# FPGA_MGT.net
KiCad netlist of a schematic drawn in Altium Designer
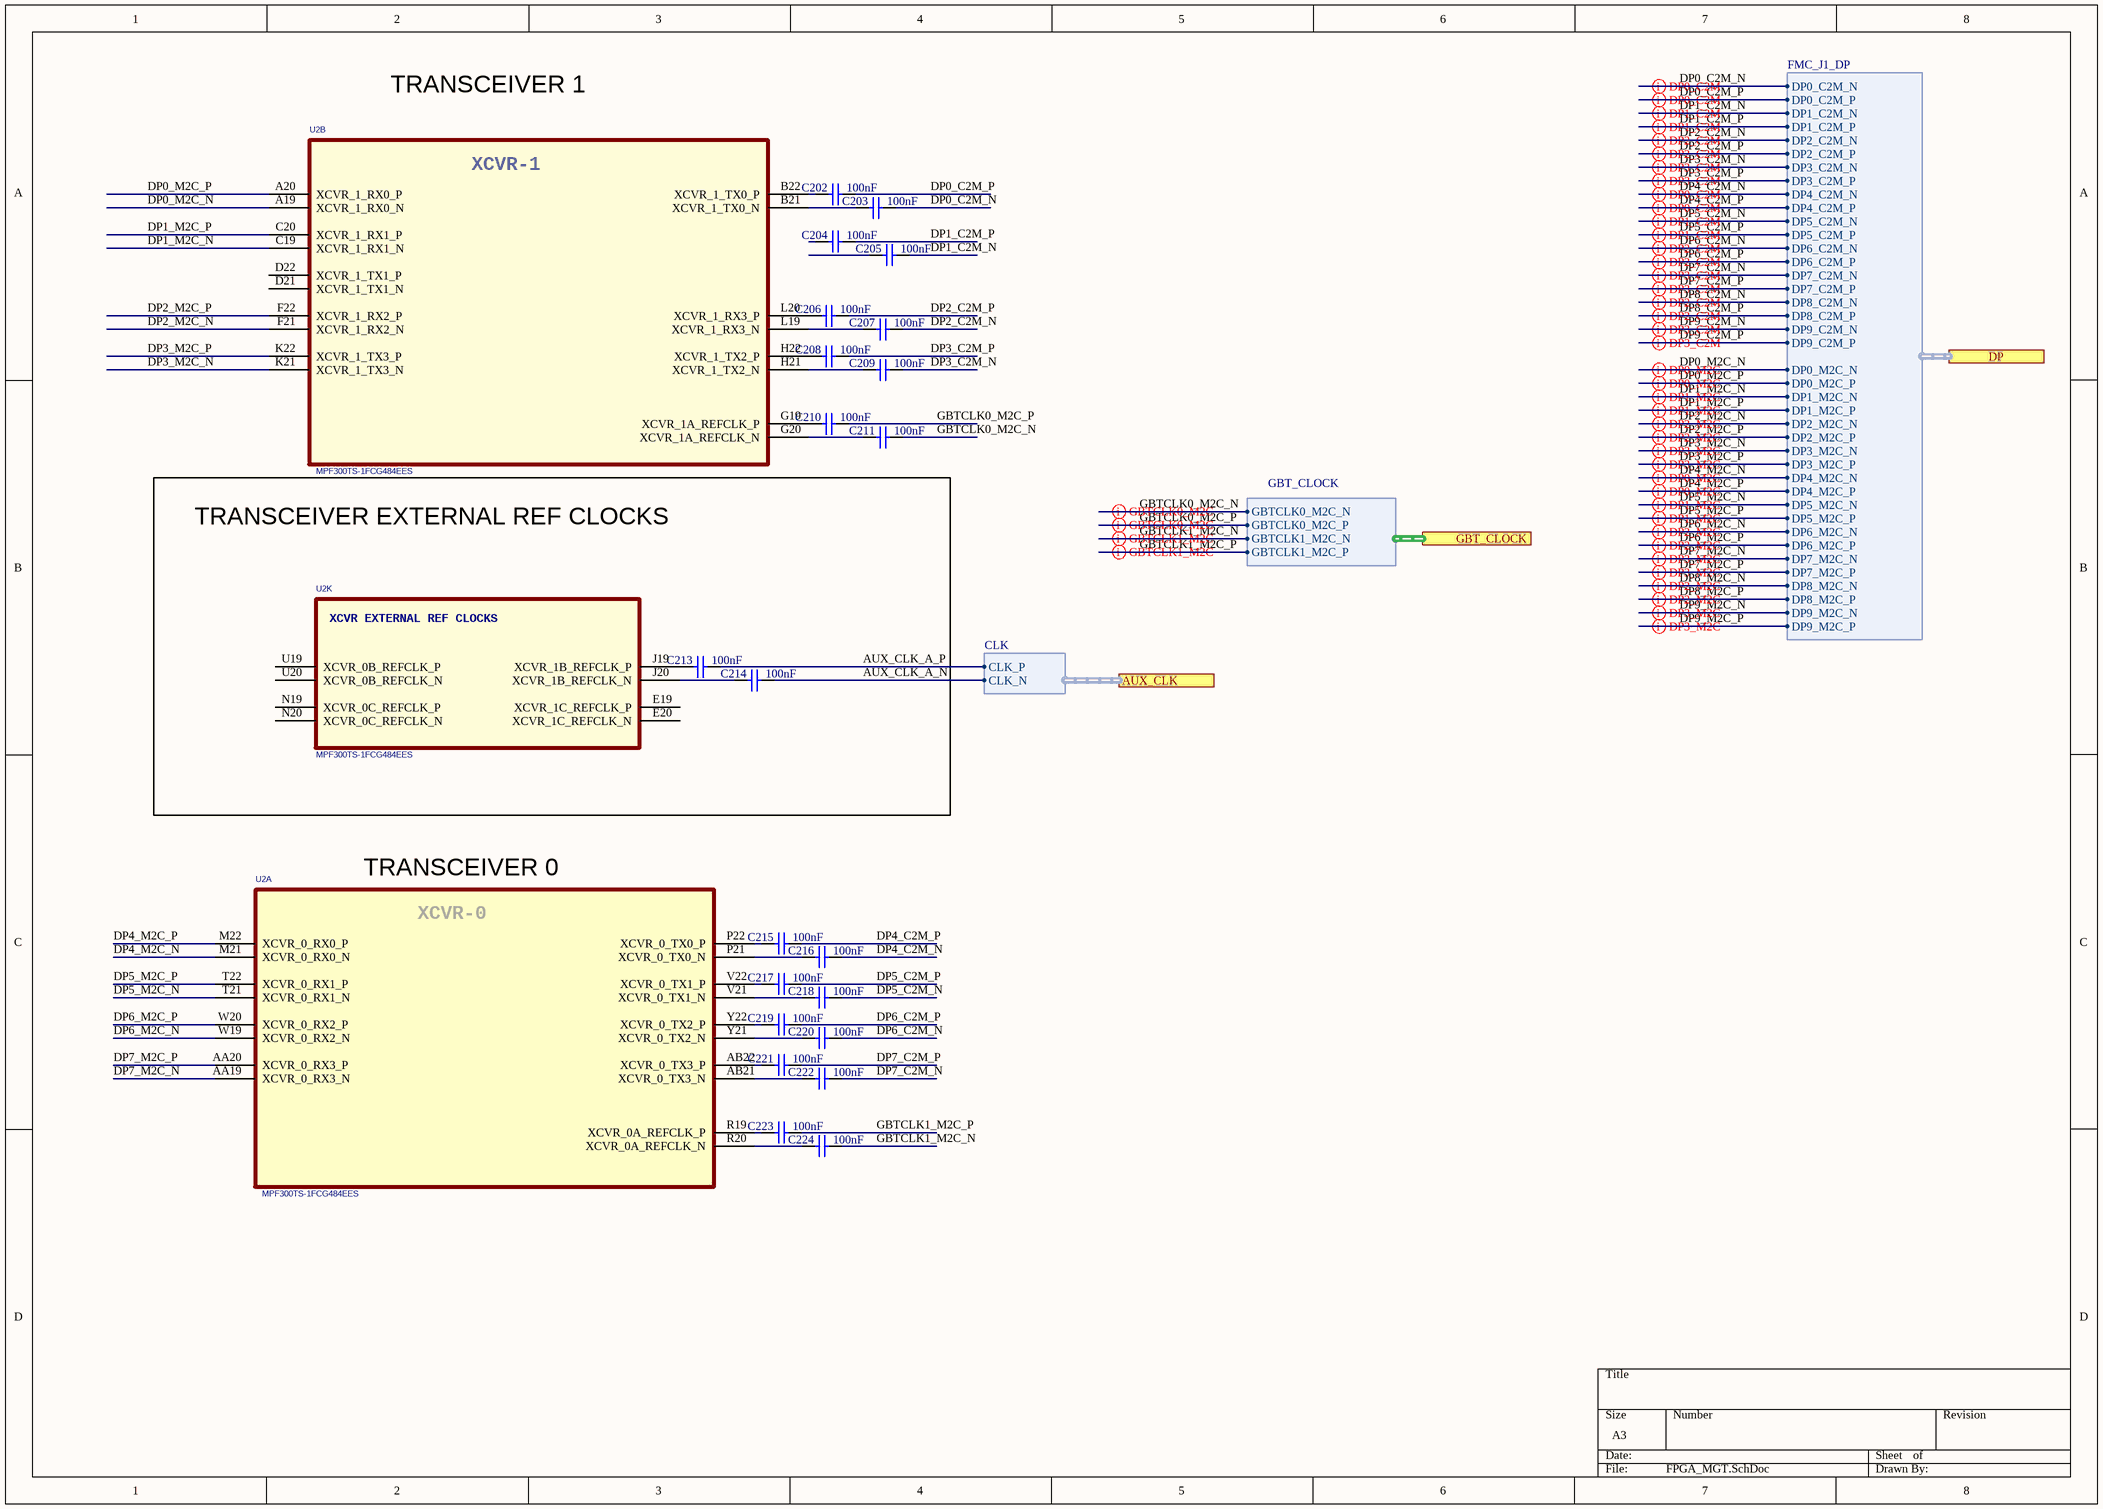
[diagram p0: FPGA_MGT.SchDoc]

(export (version "E")
  (design (tool "Eeschema 10.0.6"))
  (components
    (comp (ref "C202")
      (value "100nF")
      (footprint "CAPC0603X33N")
      (description "Non-polarised capacitor")
      (fields
        (field (name "PART NUMBER") "CC0201_100NF_6.3V_10%_X5R")
        (field (name "VOLTAGE") "6.3V")
        (field (name "AUTHOR") "CERN DEM JLC")
      )
      (libsource (lib "Capacitors") (part "Capacitor - non polarized"))
    )
    (comp (ref "C203")
      (value "100nF")
      (footprint "CAPC0603X33N")
      (description "Non-polarised capacitor")
      (fields
        (field (name "PART NUMBER") "CC0201_100NF_6.3V_10%_X5R")
        (field (name "VOLTAGE") "6.3V")
        (field (name "AUTHOR") "CERN DEM JLC")
      )
      (libsource (lib "Capacitors") (part "Capacitor - non polarized"))
    )
    (comp (ref "C204")
      (value "100nF")
      (footprint "CAPC0603X33N")
      (description "Non-polarised capacitor")
      (fields
        (field (name "PART NUMBER") "CC0201_100NF_6.3V_10%_X5R")
        (field (name "VOLTAGE") "6.3V")
        (field (name "AUTHOR") "CERN DEM JLC")
      )
      (libsource (lib "Capacitors") (part "Capacitor - non polarized"))
    )
    (comp (ref "C205")
      (value "100nF")
      (footprint "CAPC0603X33N")
      (description "Non-polarised capacitor")
      (fields
        (field (name "PART NUMBER") "CC0201_100NF_6.3V_10%_X5R")
        (field (name "VOLTAGE") "6.3V")
        (field (name "AUTHOR") "CERN DEM JLC")
      )
      (libsource (lib "Capacitors") (part "Capacitor - non polarized"))
    )
    (comp (ref "C206")
      (value "100nF")
      (footprint "CAPC0603X33N")
      (description "Non-polarised capacitor")
      (fields
        (field (name "PART NUMBER") "CC0201_100NF_6.3V_10%_X5R")
        (field (name "VOLTAGE") "6.3V")
        (field (name "AUTHOR") "CERN DEM JLC")
      )
      (libsource (lib "Capacitors") (part "Capacitor - non polarized"))
    )
    (comp (ref "C207")
      (value "100nF")
      (footprint "CAPC0603X33N")
      (description "Non-polarised capacitor")
      (fields
        (field (name "PART NUMBER") "CC0201_100NF_6.3V_10%_X5R")
        (field (name "VOLTAGE") "6.3V")
        (field (name "AUTHOR") "CERN DEM JLC")
      )
      (libsource (lib "Capacitors") (part "Capacitor - non polarized"))
    )
    (comp (ref "C208")
      (value "100nF")
      (footprint "CAPC0603X33N")
      (description "Non-polarised capacitor")
      (fields
        (field (name "PART NUMBER") "CC0201_100NF_6.3V_10%_X5R")
        (field (name "VOLTAGE") "6.3V")
        (field (name "AUTHOR") "CERN DEM JLC")
      )
      (libsource (lib "Capacitors") (part "Capacitor - non polarized"))
    )
    (comp (ref "C209")
      (value "100nF")
      (footprint "CAPC0603X33N")
      (description "Non-polarised capacitor")
      (fields
        (field (name "PART NUMBER") "CC0201_100NF_6.3V_10%_X5R")
        (field (name "VOLTAGE") "6.3V")
        (field (name "AUTHOR") "CERN DEM JLC")
      )
      (libsource (lib "Capacitors") (part "Capacitor - non polarized"))
    )
    (comp (ref "C210")
      (value "100nF")
      (footprint "CAPC0603X33N")
      (description "Non-polarised capacitor")
      (fields
        (field (name "PART NUMBER") "CC0201_100NF_6.3V_10%_X5R")
        (field (name "VOLTAGE") "6.3V")
        (field (name "AUTHOR") "CERN DEM JLC")
      )
      (libsource (lib "Capacitors") (part "Capacitor - non polarized"))
    )
    (comp (ref "C211")
      (value "100nF")
      (footprint "CAPC0603X33N")
      (description "Non-polarised capacitor")
      (fields
        (field (name "PART NUMBER") "CC0201_100NF_6.3V_10%_X5R")
        (field (name "VOLTAGE") "6.3V")
        (field (name "AUTHOR") "CERN DEM JLC")
      )
      (libsource (lib "Capacitors") (part "Capacitor - non polarized"))
    )
    (comp (ref "C213")
      (value "100nF")
      (footprint "CAPC0603X33N")
      (description "Non-polarised capacitor")
      (fields
        (field (name "PART NUMBER") "CC0201_100NF_6.3V_10%_X5R")
        (field (name "VOLTAGE") "6.3V")
        (field (name "AUTHOR") "CERN DEM JLC")
      )
      (libsource (lib "Capacitors") (part "Capacitor - non polarized"))
    )
    (comp (ref "C214")
      (value "100nF")
      (footprint "CAPC0603X33N")
      (description "Non-polarised capacitor")
      (fields
        (field (name "PART NUMBER") "CC0201_100NF_6.3V_10%_X5R")
        (field (name "VOLTAGE") "6.3V")
        (field (name "AUTHOR") "CERN DEM JLC")
      )
      (libsource (lib "Capacitors") (part "Capacitor - non polarized"))
    )
    (comp (ref "C215")
      (value "100nF")
      (footprint "CAPC0603X33N")
      (description "Non-polarised capacitor")
      (fields
        (field (name "PART NUMBER") "CC0201_100NF_6.3V_10%_X5R")
        (field (name "VOLTAGE") "6.3V")
        (field (name "AUTHOR") "CERN DEM JLC")
      )
      (libsource (lib "Capacitors") (part "Capacitor - non polarized"))
    )
    (comp (ref "C216")
      (value "100nF")
      (footprint "CAPC0603X33N")
      (description "Non-polarised capacitor")
      (fields
        (field (name "PART NUMBER") "CC0201_100NF_6.3V_10%_X5R")
        (field (name "VOLTAGE") "6.3V")
        (field (name "AUTHOR") "CERN DEM JLC")
      )
      (libsource (lib "Capacitors") (part "Capacitor - non polarized"))
    )
    (comp (ref "C217")
      (value "100nF")
      (footprint "CAPC0603X33N")
      (description "Non-polarised capacitor")
      (fields
        (field (name "PART NUMBER") "CC0201_100NF_6.3V_10%_X5R")
        (field (name "VOLTAGE") "6.3V")
        (field (name "AUTHOR") "CERN DEM JLC")
      )
      (libsource (lib "Capacitors") (part "Capacitor - non polarized"))
    )
    (comp (ref "C218")
      (value "100nF")
      (footprint "CAPC0603X33N")
      (description "Non-polarised capacitor")
      (fields
        (field (name "PART NUMBER") "CC0201_100NF_6.3V_10%_X5R")
        (field (name "VOLTAGE") "6.3V")
        (field (name "AUTHOR") "CERN DEM JLC")
      )
      (libsource (lib "Capacitors") (part "Capacitor - non polarized"))
    )
    (comp (ref "C219")
      (value "100nF")
      (footprint "CAPC0603X33N")
      (description "Non-polarised capacitor")
      (fields
        (field (name "PART NUMBER") "CC0201_100NF_6.3V_10%_X5R")
        (field (name "VOLTAGE") "6.3V")
        (field (name "AUTHOR") "CERN DEM JLC")
      )
      (libsource (lib "Capacitors") (part "Capacitor - non polarized"))
    )
    (comp (ref "C220")
      (value "100nF")
      (footprint "CAPC0603X33N")
      (description "Non-polarised capacitor")
      (fields
        (field (name "PART NUMBER") "CC0201_100NF_6.3V_10%_X5R")
        (field (name "VOLTAGE") "6.3V")
        (field (name "AUTHOR") "CERN DEM JLC")
      )
      (libsource (lib "Capacitors") (part "Capacitor - non polarized"))
    )
    (comp (ref "C221")
      (value "100nF")
      (footprint "CAPC0603X33N")
      (description "Non-polarised capacitor")
      (fields
        (field (name "PART NUMBER") "CC0201_100NF_6.3V_10%_X5R")
        (field (name "VOLTAGE") "6.3V")
        (field (name "AUTHOR") "CERN DEM JLC")
      )
      (libsource (lib "Capacitors") (part "Capacitor - non polarized"))
    )
    (comp (ref "C222")
      (value "100nF")
      (footprint "CAPC0603X33N")
      (description "Non-polarised capacitor")
      (fields
        (field (name "PART NUMBER") "CC0201_100NF_6.3V_10%_X5R")
        (field (name "VOLTAGE") "6.3V")
        (field (name "AUTHOR") "CERN DEM JLC")
      )
      (libsource (lib "Capacitors") (part "Capacitor - non polarized"))
    )
    (comp (ref "C223")
      (value "100nF")
      (footprint "CAPC0603X33N")
      (description "Non-polarised capacitor")
      (fields
        (field (name "PART NUMBER") "CC0201_100NF_6.3V_10%_X5R")
        (field (name "VOLTAGE") "6.3V")
        (field (name "AUTHOR") "CERN DEM JLC")
      )
      (libsource (lib "Capacitors") (part "Capacitor - non polarized"))
    )
    (comp (ref "C224")
      (value "100nF")
      (footprint "CAPC0603X33N")
      (description "Non-polarised capacitor")
      (fields
        (field (name "PART NUMBER") "CC0201_100NF_6.3V_10%_X5R")
        (field (name "VOLTAGE") "6.3V")
        (field (name "AUTHOR") "CERN DEM JLC")
      )
      (libsource (lib "Capacitors") (part "Capacitor - non polarized"))
    )
    (comp (ref "U2")
      (value "MPF300TS-1FCG484EES")
      (footprint "BGA484C100P22X22_2300X2300X320")
      (description "FCG484,23mmX23mm,1.0mm pitch")
      (fields (field (name "MANUFACTURER") "Microsemi") (field (name "PART NUMBER") "MPF300TS-1FCG484I"))
      (libsource (lib "LIBRARY_SCH") (part "FPGA_MPF300T-FCG484"))
    )
  )
  (nets
    (net (code "4") (name "/AUX_CLK_A_N") (class "Default")
      (node (ref "C214") (pin "2") (pinfunction "2_2") (pintype "passive"))
    )
    (net (code "5") (name "/AUX_CLK_A_P") (class "Default")
      (node (ref "C213") (pin "2") (pinfunction "2_2") (pintype "passive"))
    )
    (net (code "6") (name "/DP0_C2M_N") (class "Default")
      (node (ref "C203") (pin "2") (pinfunction "2_2") (pintype "passive"))
    )
    (net (code "7") (name "/DP0_C2M_P") (class "Default")
      (node (ref "C202") (pin "2") (pinfunction "2_2") (pintype "passive"))
    )
    (net (code "8") (name "/DP0_M2C_N") (class "Default")
      (node (ref "U2") (pin "A19") (pinfunction "XCVR_1_RX0_N_A19") (pintype "passive"))
    )
    (net (code "9") (name "/DP0_M2C_P") (class "Default")
      (node (ref "U2") (pin "A20") (pinfunction "XCVR_1_RX0_P_A20") (pintype "passive"))
    )
    (net (code "10") (name "/DP1_C2M_N") (class "Default")
      (node (ref "C205") (pin "2") (pinfunction "2_2") (pintype "passive"))
    )
    (net (code "11") (name "/DP1_C2M_P") (class "Default")
      (node (ref "C204") (pin "2") (pinfunction "2_2") (pintype "passive"))
    )
    (net (code "12") (name "/DP1_M2C_N") (class "Default")
      (node (ref "U2") (pin "C19") (pinfunction "XCVR_1_RX1_N_C19") (pintype "passive"))
    )
    (net (code "13") (name "/DP1_M2C_P") (class "Default")
      (node (ref "U2") (pin "C20") (pinfunction "XCVR_1_RX1_P_C20") (pintype "passive"))
    )
    (net (code "14") (name "/DP2_C2M_N") (class "Default")
      (node (ref "C207") (pin "2") (pinfunction "2_2") (pintype "passive"))
    )
    (net (code "15") (name "/DP2_C2M_P") (class "Default")
      (node (ref "C206") (pin "2") (pinfunction "2_2") (pintype "passive"))
    )
    (net (code "16") (name "/DP2_M2C_N") (class "Default")
      (node (ref "U2") (pin "F21") (pinfunction "XCVR_1_RX2_N_F21") (pintype "passive"))
    )
    (net (code "17") (name "/DP2_M2C_P") (class "Default")
      (node (ref "U2") (pin "F22") (pinfunction "XCVR_1_RX2_P_F22") (pintype "passive"))
    )
    (net (code "18") (name "/DP3_C2M_N") (class "Default")
      (node (ref "C209") (pin "2") (pinfunction "2_2") (pintype "passive"))
    )
    (net (code "19") (name "/DP3_C2M_P") (class "Default")
      (node (ref "C208") (pin "2") (pinfunction "2_2") (pintype "passive"))
    )
    (net (code "20") (name "/DP3_M2C_N") (class "Default")
      (node (ref "U2") (pin "K21") (pinfunction "XCVR_1_TX3_N_K21") (pintype "passive"))
    )
    (net (code "21") (name "/DP3_M2C_P") (class "Default")
      (node (ref "U2") (pin "K22") (pinfunction "XCVR_1_TX3_P_K22") (pintype "passive"))
    )
    (net (code "22") (name "/DP4_C2M_N") (class "Default")
      (node (ref "C216") (pin "2") (pinfunction "2_2") (pintype "passive"))
    )
    (net (code "23") (name "/DP4_C2M_P") (class "Default")
      (node (ref "C215") (pin "2") (pinfunction "2_2") (pintype "passive"))
    )
    (net (code "24") (name "/DP4_M2C_N") (class "Default")
      (node (ref "U2") (pin "M21") (pinfunction "XCVR_0_RX0_N_M21") (pintype "passive"))
    )
    (net (code "25") (name "/DP4_M2C_P") (class "Default")
      (node (ref "U2") (pin "M22") (pinfunction "XCVR_0_RX0_P_M22") (pintype "passive"))
    )
    (net (code "26") (name "/DP5_C2M_N") (class "Default")
      (node (ref "C218") (pin "2") (pinfunction "2_2") (pintype "passive"))
    )
    (net (code "27") (name "/DP5_C2M_P") (class "Default")
      (node (ref "C217") (pin "2") (pinfunction "2_2") (pintype "passive"))
    )
    (net (code "28") (name "/DP5_M2C_N") (class "Default")
      (node (ref "U2") (pin "T21") (pinfunction "XCVR_0_RX1_N_T21") (pintype "passive"))
    )
    (net (code "29") (name "/DP5_M2C_P") (class "Default")
      (node (ref "U2") (pin "T22") (pinfunction "XCVR_0_RX1_P_T22") (pintype "passive"))
    )
    (net (code "30") (name "/DP6_C2M_N") (class "Default")
      (node (ref "C220") (pin "2") (pinfunction "2_2") (pintype "passive"))
    )
    (net (code "31") (name "/DP6_C2M_P") (class "Default")
      (node (ref "C219") (pin "2") (pinfunction "2_2") (pintype "passive"))
    )
    (net (code "32") (name "/DP6_M2C_N") (class "Default")
      (node (ref "U2") (pin "W19") (pinfunction "XCVR_0_RX2_N_W19") (pintype "passive"))
    )
    (net (code "33") (name "/DP6_M2C_P") (class "Default")
      (node (ref "U2") (pin "W20") (pinfunction "XCVR_0_RX2_P_W20") (pintype "passive"))
    )
    (net (code "34") (name "/DP7_C2M_N") (class "Default")
      (node (ref "C222") (pin "2") (pinfunction "2_2") (pintype "passive"))
    )
    (net (code "35") (name "/DP7_C2M_P") (class "Default")
      (node (ref "C221") (pin "2") (pinfunction "2_2") (pintype "passive"))
    )
    (net (code "36") (name "/DP7_M2C_N") (class "Default")
      (node (ref "U2") (pin "AA19") (pinfunction "XCVR_0_RX3_N_AA19") (pintype "passive"))
    )
    (net (code "37") (name "/DP7_M2C_P") (class "Default")
      (node (ref "U2") (pin "AA20") (pinfunction "XCVR_0_RX3_P_AA20") (pintype "passive"))
    )
    (net (code "46") (name "/GBTCLK0_M2C_N") (class "Default")
      (node (ref "C211") (pin "2") (pinfunction "2_2") (pintype "passive"))
    )
    (net (code "47") (name "/GBTCLK0_M2C_P") (class "Default")
      (node (ref "C210") (pin "2") (pinfunction "2_2") (pintype "passive"))
    )
    (net (code "48") (name "/GBTCLK1_M2C_N") (class "Default")
      (node (ref "C224") (pin "2") (pinfunction "2_2") (pintype "passive"))
    )
    (net (code "49") (name "/GBTCLK1_M2C_P") (class "Default")
      (node (ref "C223") (pin "2") (pinfunction "2_2") (pintype "passive"))
    )
    (net (code "53") (name "Net-(U2A-XCVR_0A_REFCLK_N)") (class "Default")
      (node (ref "C224") (pin "1") (pinfunction "1_1") (pintype "passive"))
      (node (ref "U2") (pin "R20") (pinfunction "XCVR_0A_REFCLK_N_R20") (pintype "passive"))
    )
    (net (code "54") (name "Net-(U2A-XCVR_0A_REFCLK_P)") (class "Default")
      (node (ref "C223") (pin "1") (pinfunction "1_1") (pintype "passive"))
      (node (ref "U2") (pin "R19") (pinfunction "XCVR_0A_REFCLK_P_R19") (pintype "passive"))
    )
    (net (code "55") (name "Net-(U2A-XCVR_0_TX0_N)") (class "Default")
      (node (ref "C216") (pin "1") (pinfunction "1_1") (pintype "passive"))
      (node (ref "U2") (pin "P21") (pinfunction "XCVR_0_TX0_N_P21") (pintype "passive"))
    )
    (net (code "56") (name "Net-(U2A-XCVR_0_TX0_P)") (class "Default")
      (node (ref "C215") (pin "1") (pinfunction "1_1") (pintype "passive"))
      (node (ref "U2") (pin "P22") (pinfunction "XCVR_0_TX0_P_P22") (pintype "passive"))
    )
    (net (code "57") (name "Net-(U2A-XCVR_0_TX1_N)") (class "Default")
      (node (ref "C218") (pin "1") (pinfunction "1_1") (pintype "passive"))
      (node (ref "U2") (pin "V21") (pinfunction "XCVR_0_TX1_N_V21") (pintype "passive"))
    )
    (net (code "58") (name "Net-(U2A-XCVR_0_TX1_P)") (class "Default")
      (node (ref "C217") (pin "1") (pinfunction "1_1") (pintype "passive"))
      (node (ref "U2") (pin "V22") (pinfunction "XCVR_0_TX1_P_V22") (pintype "passive"))
    )
    (net (code "59") (name "Net-(U2A-XCVR_0_TX2_N)") (class "Default")
      (node (ref "C220") (pin "1") (pinfunction "1_1") (pintype "passive"))
      (node (ref "U2") (pin "Y21") (pinfunction "XCVR_0_TX2_N_Y21") (pintype "passive"))
    )
    (net (code "60") (name "Net-(U2A-XCVR_0_TX2_P)") (class "Default")
      (node (ref "C219") (pin "1") (pinfunction "1_1") (pintype "passive"))
      (node (ref "U2") (pin "Y22") (pinfunction "XCVR_0_TX2_P_Y22") (pintype "passive"))
    )
    (net (code "61") (name "Net-(U2A-XCVR_0_TX3_N)") (class "Default")
      (node (ref "C222") (pin "1") (pinfunction "1_1") (pintype "passive"))
      (node (ref "U2") (pin "AB21") (pinfunction "XCVR_0_TX3_N_AB21") (pintype "passive"))
    )
    (net (code "62") (name "Net-(U2A-XCVR_0_TX3_P)") (class "Default")
      (node (ref "C221") (pin "1") (pinfunction "1_1") (pintype "passive"))
      (node (ref "U2") (pin "AB22") (pinfunction "XCVR_0_TX3_P_AB22") (pintype "passive"))
    )
    (net (code "63") (name "Net-(U2B-XCVR_1A_REFCLK_N)") (class "Default")
      (node (ref "C211") (pin "1") (pinfunction "1_1") (pintype "passive"))
      (node (ref "U2") (pin "G20") (pinfunction "XCVR_1A_REFCLK_N_G20") (pintype "passive"))
    )
    (net (code "64") (name "Net-(U2B-XCVR_1A_REFCLK_P)") (class "Default")
      (node (ref "C210") (pin "1") (pinfunction "1_1") (pintype "passive"))
      (node (ref "U2") (pin "G19") (pinfunction "XCVR_1A_REFCLK_P_G19") (pintype "passive"))
    )
    (net (code "65") (name "Net-(U2B-XCVR_1_RX3_N)") (class "Default")
      (node (ref "C207") (pin "1") (pinfunction "1_1") (pintype "passive"))
      (node (ref "U2") (pin "L19") (pinfunction "XCVR_1_RX3_N_L19") (pintype "passive"))
    )
    (net (code "66") (name "Net-(U2B-XCVR_1_RX3_P)") (class "Default")
      (node (ref "C206") (pin "1") (pinfunction "1_1") (pintype "passive"))
      (node (ref "U2") (pin "L20") (pinfunction "XCVR_1_RX3_P_L20") (pintype "passive"))
    )
    (net (code "67") (name "Net-(U2B-XCVR_1_TX0_N)") (class "Default")
      (node (ref "C203") (pin "1") (pinfunction "1_1") (pintype "passive"))
      (node (ref "U2") (pin "B21") (pinfunction "XCVR_1_TX0_N_B21") (pintype "passive"))
    )
    (net (code "68") (name "Net-(U2B-XCVR_1_TX0_P)") (class "Default")
      (node (ref "C202") (pin "1") (pinfunction "1_1") (pintype "passive"))
      (node (ref "U2") (pin "B22") (pinfunction "XCVR_1_TX0_P_B22") (pintype "passive"))
    )
    (net (code "69") (name "Net-(U2B-XCVR_1_TX2_N)") (class "Default")
      (node (ref "C209") (pin "1") (pinfunction "1_1") (pintype "passive"))
      (node (ref "U2") (pin "H21") (pinfunction "XCVR_1_TX2_N_H21") (pintype "passive"))
    )
    (net (code "70") (name "Net-(U2B-XCVR_1_TX2_P)") (class "Default")
      (node (ref "C208") (pin "1") (pinfunction "1_1") (pintype "passive"))
      (node (ref "U2") (pin "H22") (pinfunction "XCVR_1_TX2_P_H22") (pintype "passive"))
    )
    (net (code "71") (name "Net-(U2K-XCVR_1B_REFCLK_N)") (class "Default")
      (node (ref "C214") (pin "1") (pinfunction "1_1") (pintype "passive"))
      (node (ref "U2") (pin "J20") (pinfunction "XCVR_1B_REFCLK_N_J20") (pintype "passive"))
    )
    (net (code "72") (name "Net-(U2K-XCVR_1B_REFCLK_P)") (class "Default")
      (node (ref "C213") (pin "1") (pinfunction "1_1") (pintype "passive"))
      (node (ref "U2") (pin "J19") (pinfunction "XCVR_1B_REFCLK_P_J19") (pintype "passive"))
    )
    (net (code "73") (name "unconnected-(C204-Pad1)") (class "Default")
      (node (ref "C204") (pin "1") (pinfunction "1_1") (pintype "passive"))
    )
    (net (code "74") (name "unconnected-(C205-Pad1)") (class "Default")
      (node (ref "C205") (pin "1") (pinfunction "1_1") (pintype "passive"))
    )
    (net (code "75") (name "unconnected-(U2B-XCVR_1_TX1_N-PadD21)") (class "Default")
      (node (ref "U2") (pin "D21") (pinfunction "XCVR_1_TX1_N_D21") (pintype "passive"))
    )
    (net (code "76") (name "unconnected-(U2B-XCVR_1_TX1_P-PadD22)") (class "Default")
      (node (ref "U2") (pin "D22") (pinfunction "XCVR_1_TX1_P_D22") (pintype "passive"))
    )
    (net (code "77") (name "unconnected-(U2K-XCVR_0B_REFCLK_N-PadU20)") (class "Default")
      (node (ref "U2") (pin "U20") (pinfunction "XCVR_0B_REFCLK_N_U20") (pintype "passive"))
    )
    (net (code "78") (name "unconnected-(U2K-XCVR_0B_REFCLK_P-PadU19)") (class "Default")
      (node (ref "U2") (pin "U19") (pinfunction "XCVR_0B_REFCLK_P_U19") (pintype "passive"))
    )
    (net (code "79") (name "unconnected-(U2K-XCVR_0C_REFCLK_N-PadN20)") (class "Default")
      (node (ref "U2") (pin "N20") (pinfunction "XCVR_0C_REFCLK_N_N20") (pintype "passive"))
    )
    (net (code "80") (name "unconnected-(U2K-XCVR_0C_REFCLK_P-PadN19)") (class "Default")
      (node (ref "U2") (pin "N19") (pinfunction "XCVR_0C_REFCLK_P_N19") (pintype "passive"))
    )
    (net (code "81") (name "unconnected-(U2K-XCVR_1C_REFCLK_N-PadE20)") (class "Default")
      (node (ref "U2") (pin "E20") (pinfunction "XCVR_1C_REFCLK_N_E20") (pintype "passive"))
    )
    (net (code "82") (name "unconnected-(U2K-XCVR_1C_REFCLK_P-PadE19)") (class "Default")
      (node (ref "U2") (pin "E19") (pinfunction "XCVR_1C_REFCLK_P_E19") (pintype "passive"))
    )
  )
)
